# Sheet5.net
KiCad netlist of a schematic drawn in Altium Designer
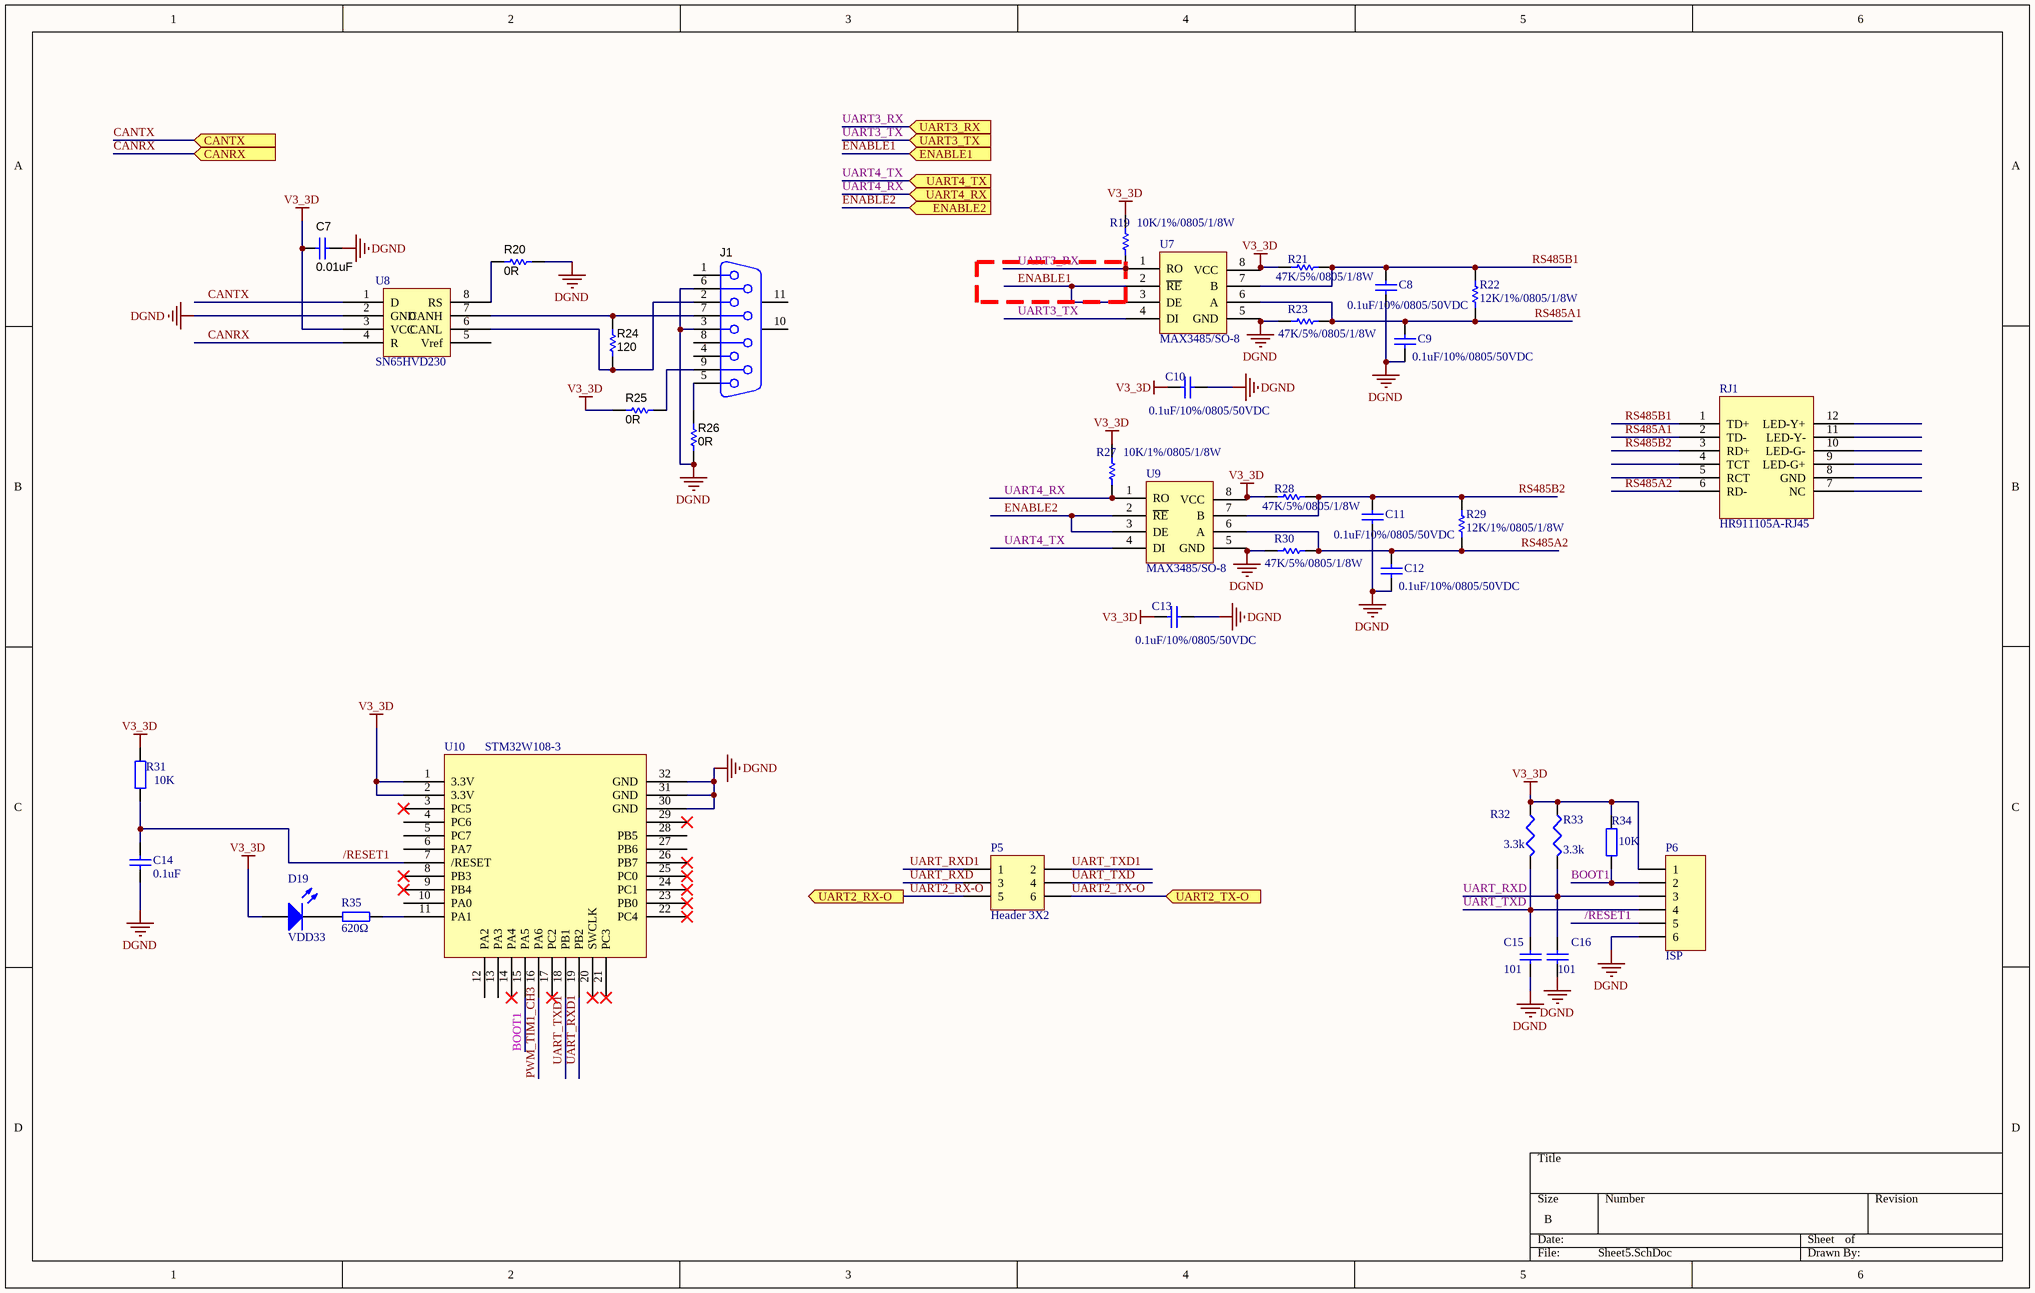
[diagram p0: Sheet5.SchDoc]

(export (version "E")
  (design (tool "Eeschema 10.0.6"))
  (components
    (comp (ref "C7")
      (value "~")
      (footprint "0805_cap")
      (description "CAP, CERM, 0.01uF, 16V, +/-10%, X7R, 0402")
      (fields
        (field (name "PARTNUMBER") "C1005X7R1C103K")
        (field (name "VALUEDISPLAYED") "0.01uF")
        (field (name "MANUFACTURER") "TDK")
        (field (name "PUBLISHER") "Texas Instruments")
      )
      (libsource (lib "Capacitor_Ceramic") (part "C1005X7R1C103K"))
    )
    (comp (ref "C8")
      (value "0.1uF/10%/0805/50VDC")
      (footprint "C-0805")
      (libsource (lib "浙江关西电机数据库") (part "CAP_Non-polarity"))
    )
    (comp (ref "C9")
      (value "0.1uF/10%/0805/50VDC")
      (footprint "C-0805")
      (libsource (lib "浙江关西电机数据库") (part "CAP_Non-polarity"))
    )
    (comp (ref "C10")
      (value "0.1uF/10%/0805/50VDC")
      (footprint "C-0805")
      (libsource (lib "浙江关西电机数据库") (part "CAP_Non-polarity"))
    )
    (comp (ref "C11")
      (value "0.1uF/10%/0805/50VDC")
      (footprint "C-0805")
      (libsource (lib "浙江关西电机数据库") (part "CAP_Non-polarity"))
    )
    (comp (ref "C12")
      (value "0.1uF/10%/0805/50VDC")
      (footprint "C-0805")
      (libsource (lib "浙江关西电机数据库") (part "CAP_Non-polarity"))
    )
    (comp (ref "C13")
      (value "0.1uF/10%/0805/50VDC")
      (footprint "C-0805")
      (libsource (lib "浙江关西电机数据库") (part "CAP_Non-polarity"))
    )
    (comp (ref "C14")
      (value "0.1uF")
      (footprint "C0805")
      (description "Capacitor")
      (fields (field (name "PUBLISHER") "Altium Limited"))
      (libsource (lib "Miscellaneous Devices") (part "Cap"))
    )
    (comp (ref "C15")
      (value "101")
      (footprint "C0805")
      (description "Capacitor")
      (fields (field (name "PUBLISHER") "Altium Limited"))
      (libsource (lib "Miscellaneous Devices") (part "Cap"))
    )
    (comp (ref "C16")
      (value "101")
      (footprint "C0805")
      (description "Capacitor")
      (fields (field (name "PUBLISHER") "Altium Limited"))
      (libsource (lib "Miscellaneous Devices") (part "Cap"))
    )
    (comp (ref "D19")
      (value "VDD33")
      (footprint "0805LED")
      (description "Typical BLUE SiC LED")
      (fields (field (name "PUBLISHER") "Altium Limited"))
      (libsource (lib "Miscellaneous Devices") (part "LED3"))
    )
    (comp (ref "J1")
      (value "~")
      (footprint "CONN_1734348-1")
      (description "Conn D-SUB RCPT R/A 9POS GOLD/FL, TH")
      (fields
        (field (name "PARTNUMBER") "1734348-1")
        (field (name "MANUFACTURER") "TE Connectivity")
        (field (name "SYMBOLCREATOR") "a0412235")
        (field (name "PUBLISHER") "Texas Instruments")
      )
      (libsource (lib "Connectors") (part "1734348-1"))
    )
    (comp (ref "P5")
      (value "Header 3X2")
      (footprint "HDR2X3")
      (description "Header, 3-Pin, Dual row")
      (fields (field (name "PUBLISHER") "Altium Limited"))
      (libsource (lib "Miscellaneous Connectors") (part "Header 3X2"))
    )
    (comp (ref "P6")
      (value "ISP")
      (footprint "SIP-6B")
      (description "Header, 6-Pin")
      (fields (field (name "PUBLISHER") "Altium Limited"))
      (libsource (lib "Miscellaneous Connectors") (part "Header 6"))
    )
    (comp (ref "R19")
      (value "10K/1%/0805/1/8W")
      (footprint "R-0805")
      (fields (field (name "PART NUMBER") "ASR-0028BA"))
      (libsource (lib "浙江关西电机数据库") (part "RES_1"))
    )
    (comp (ref "R20")
      (value "0R")
      (footprint "0805_HV")
      (description "RES, 60.4 ohm, 1%, 0.125W, 0805")
      (fields
        (field (name "PARTNUMBER") "CRCW080560R4FKEA")
        (field (name "MANUFACTURER") "Vishay-Dale")
        (field (name "PUBLISHER") "Texas Instruments")
      )
      (libsource (lib "Resistor_0805") (part "CRCW080560R4FKEA"))
    )
    (comp (ref "R21")
      (value "47K/5%/0805/1/8W")
      (footprint "R-0805")
      (fields (field (name "PART NUMBER") "ASR-0134BA"))
      (libsource (lib "浙江关西电机数据库") (part "RES_1"))
    )
    (comp (ref "R22")
      (value "12K/1%/0805/1/8W")
      (footprint "R-0805")
      (libsource (lib "浙江关西电机数据库") (part "RES_1"))
    )
    (comp (ref "R23")
      (value "47K/5%/0805/1/8W")
      (footprint "R-0805")
      (fields (field (name "PART NUMBER") "ASR-0134BA"))
      (libsource (lib "浙江关西电机数据库") (part "RES_1"))
    )
    (comp (ref "R24")
      (value "120")
      (footprint "0805_HV")
      (description "RES, 60.4 ohm, 1%, 0.125W, 0805")
      (fields
        (field (name "PARTNUMBER") "CRCW080560R4FKEA")
        (field (name "MANUFACTURER") "Vishay-Dale")
        (field (name "PUBLISHER") "Texas Instruments")
      )
      (libsource (lib "Resistor_0805") (part "CRCW080560R4FKEA"))
    )
    (comp (ref "R25")
      (value "0R")
      (footprint "0805_HV")
      (description "RES, 60.4 ohm, 1%, 0.125W, 0805")
      (fields
        (field (name "PARTNUMBER") "CRCW080560R4FKEA")
        (field (name "MANUFACTURER") "Vishay-Dale")
        (field (name "PUBLISHER") "Texas Instruments")
      )
      (libsource (lib "Resistor_0805") (part "CRCW080560R4FKEA"))
    )
    (comp (ref "R26")
      (value "0R")
      (footprint "0805_HV")
      (description "RES, 60.4 ohm, 1%, 0.125W, 0805")
      (fields
        (field (name "PARTNUMBER") "CRCW080560R4FKEA")
        (field (name "MANUFACTURER") "Vishay-Dale")
        (field (name "PUBLISHER") "Texas Instruments")
      )
      (libsource (lib "Resistor_0805") (part "CRCW080560R4FKEA"))
    )
    (comp (ref "R27")
      (value "10K/1%/0805/1/8W")
      (footprint "R-0805")
      (fields (field (name "PART NUMBER") "ASR-0028BA"))
      (libsource (lib "浙江关西电机数据库") (part "RES_1"))
    )
    (comp (ref "R28")
      (value "47K/5%/0805/1/8W")
      (footprint "R-0805")
      (fields (field (name "PART NUMBER") "ASR-0134BA"))
      (libsource (lib "浙江关西电机数据库") (part "RES_1"))
    )
    (comp (ref "R29")
      (value "12K/1%/0805/1/8W")
      (footprint "R-0805")
      (libsource (lib "浙江关西电机数据库") (part "RES_1"))
    )
    (comp (ref "R30")
      (value "47K/5%/0805/1/8W")
      (footprint "R-0805")
      (fields (field (name "PART NUMBER") "ASR-0134BA"))
      (libsource (lib "浙江关西电机数据库") (part "RES_1"))
    )
    (comp (ref "R31")
      (value "10K")
      (footprint "0805")
      (description "Resistor")
      (fields (field (name "Comment") "Res2") (field (name "PUBLISHER") "Altium Limited"))
      (libsource (lib "Miscellaneous Devices") (part "Res2"))
    )
    (comp (ref "R32")
      (value "3.3k")
      (footprint "R0805")
      (description "Resistor")
      (fields (field (name "PUBLISHER") "Altium Limited"))
      (libsource (lib "Miscellaneous Devices") (part "Res3"))
    )
    (comp (ref "R33")
      (value "3.3k")
      (footprint "R0805")
      (description "Resistor")
      (fields (field (name "PUBLISHER") "Altium Limited"))
      (libsource (lib "Miscellaneous Devices") (part "Res3"))
    )
    (comp (ref "R34")
      (value "10K")
      (footprint "R0805")
      (description "Resistor")
      (fields (field (name "Comment") "Res2") (field (name "PUBLISHER") "Altium Limited"))
      (libsource (lib "Miscellaneous Devices") (part "Res2"))
    )
    (comp (ref "R35")
      (value "620Ω")
      (footprint "R0805")
      (description "R")
      (libsource (lib "Haze") (part "RES"))
    )
    (comp (ref "RJ1")
      (value "HR911105A-RJ45")
      (footprint "HR911105A")
      (libsource (lib "moonlight") (part "HR911105A-RJ45"))
    )
    (comp (ref "U7")
      (value "MAX3485/SO-8")
      (footprint "SO-G8")
      (libsource (lib "SCHLIBRARIES") (part "MAX485"))
    )
    (comp (ref "U8")
      (value "SN65HVD230")
      (footprint "SO-G8")
      (libsource (lib "SCHLIBRARIES") (part "SN65HVD230"))
    )
    (comp (ref "U9")
      (value "MAX3485/SO-8")
      (footprint "SO-G8")
      (libsource (lib "SCHLIBRARIES") (part "MAX485"))
    )
    (comp (ref "U10")
      (value "STM32W108-3")
      (footprint "STM32W108-3")
      (libsource (lib "STM32W108-3") (part "STM32W108-3"))
    )
  )
  (nets
    (net (code "1") (name "/BOOT1") (class "Default")
      (node (ref "P6") (pin "2") (pinfunction "2_2") (pintype "passive"))
      (node (ref "R34") (pin "1") (pinfunction "1_1") (pintype "passive"))
      (node (ref "U10") (pin "15") (pinfunction "PA5_15") (pintype "passive"))
    )
    (net (code "2") (name "/CANRX") (class "Default")
      (node (ref "U8") (pin "4") (pinfunction "R_4") (pintype "passive"))
    )
    (net (code "3") (name "/CANTX") (class "Default")
      (node (ref "U8") (pin "1") (pinfunction "D_1") (pintype "passive"))
    )
    (net (code "4") (name "/ENABLE1") (class "Default")
      (node (ref "U7") (pin "2") (pinfunction "~{RE}_2") (pintype "passive"))
      (node (ref "U7") (pin "3") (pinfunction "DE_3") (pintype "passive"))
    )
    (net (code "5") (name "/ENABLE2") (class "Default")
      (node (ref "U9") (pin "2") (pinfunction "~{RE}_2") (pintype "passive"))
      (node (ref "U9") (pin "3") (pinfunction "DE_3") (pintype "passive"))
    )
    (net (code "6") (name "/PWM_TIM1_CH3") (class "Default")
      (node (ref "U10") (pin "16") (pinfunction "PA6_16") (pintype "passive"))
    )
    (net (code "7") (name "/RS485A1") (class "Default")
      (node (ref "C9") (pin "2") (pinfunction "2_2") (pintype "passive"))
      (node (ref "R22") (pin "1") (pinfunction "1_1") (pintype "passive"))
      (node (ref "R23") (pin "1") (pinfunction "1_1") (pintype "passive"))
      (node (ref "RJ1") (pin "2") (pinfunction "TD-_2") (pintype "passive"))
      (node (ref "U7") (pin "6") (pinfunction "A_6") (pintype "passive"))
    )
    (net (code "8") (name "/RS485A2") (class "Default")
      (node (ref "C12") (pin "2") (pinfunction "2_2") (pintype "passive"))
      (node (ref "R29") (pin "1") (pinfunction "1_1") (pintype "passive"))
      (node (ref "R30") (pin "1") (pinfunction "1_1") (pintype "passive"))
      (node (ref "RJ1") (pin "6") (pinfunction "RD-_6") (pintype "passive"))
      (node (ref "U9") (pin "6") (pinfunction "A_6") (pintype "passive"))
    )
    (net (code "9") (name "/RS485B1") (class "Default")
      (node (ref "C8") (pin "2") (pinfunction "2_2") (pintype "passive"))
      (node (ref "R21") (pin "1") (pinfunction "1_1") (pintype "passive"))
      (node (ref "R22") (pin "2") (pinfunction "2_2") (pintype "passive"))
      (node (ref "RJ1") (pin "1") (pinfunction "TD+_1") (pintype "passive"))
      (node (ref "U7") (pin "7") (pinfunction "B_7") (pintype "passive"))
    )
    (net (code "10") (name "/RS485B2") (class "Default")
      (node (ref "C11") (pin "2") (pinfunction "2_2") (pintype "passive"))
      (node (ref "R28") (pin "1") (pinfunction "1_1") (pintype "passive"))
      (node (ref "R29") (pin "2") (pinfunction "2_2") (pintype "passive"))
      (node (ref "RJ1") (pin "3") (pinfunction "RD+_3") (pintype "passive"))
      (node (ref "U9") (pin "7") (pinfunction "B_7") (pintype "passive"))
    )
    (net (code "11") (name "/UART2_RX-O") (class "Default")
      (node (ref "P5") (pin "5") (pinfunction "5_5") (pintype "passive"))
    )
    (net (code "12") (name "/UART2_TX-O") (class "Default")
      (node (ref "P5") (pin "6") (pinfunction "6_6") (pintype "passive"))
    )
    (net (code "13") (name "/UART3_RX") (class "Default")
      (node (ref "R19") (pin "1") (pinfunction "1_1") (pintype "passive"))
      (node (ref "U7") (pin "1") (pinfunction "RO_1") (pintype "passive"))
    )
    (net (code "14") (name "/UART3_TX") (class "Default")
      (node (ref "U7") (pin "4") (pinfunction "DI_4") (pintype "passive"))
    )
    (net (code "15") (name "/UART4_RX") (class "Default")
      (node (ref "R27") (pin "1") (pinfunction "1_1") (pintype "passive"))
      (node (ref "U9") (pin "1") (pinfunction "RO_1") (pintype "passive"))
    )
    (net (code "16") (name "/UART4_TX") (class "Default")
      (node (ref "U9") (pin "4") (pinfunction "DI_4") (pintype "passive"))
    )
    (net (code "17") (name "/UART_RXD") (class "Default")
      (node (ref "C16") (pin "2") (pinfunction "2_2") (pintype "passive"))
      (node (ref "P5") (pin "3") (pinfunction "3_3") (pintype "passive"))
      (node (ref "P6") (pin "3") (pinfunction "3_3") (pintype "passive"))
      (node (ref "R33") (pin "2") (pinfunction "2_2") (pintype "passive"))
    )
    (net (code "18") (name "/UART_RXD1") (class "Default")
      (node (ref "P5") (pin "1") (pinfunction "1_1") (pintype "passive"))
      (node (ref "U10") (pin "19") (pinfunction "PB2_19") (pintype "passive"))
    )
    (net (code "19") (name "/UART_TXD") (class "Default")
      (node (ref "C15") (pin "2") (pinfunction "2_2") (pintype "passive"))
      (node (ref "P5") (pin "4") (pinfunction "4_4") (pintype "passive"))
      (node (ref "P6") (pin "4") (pinfunction "4_4") (pintype "passive"))
      (node (ref "R32") (pin "2") (pinfunction "2_2") (pintype "passive"))
    )
    (net (code "20") (name "/UART_TXD1") (class "Default")
      (node (ref "P5") (pin "2") (pinfunction "2_2") (pintype "passive"))
      (node (ref "U10") (pin "18") (pinfunction "PB1_18") (pintype "passive"))
    )
    (net (code "21") (name "/{slash}RESET1") (class "Default")
      (node (ref "C14") (pin "2") (pinfunction "2_2") (pintype "passive"))
      (node (ref "P6") (pin "5") (pinfunction "5_5") (pintype "passive"))
      (node (ref "R31") (pin "1") (pinfunction "1_1") (pintype "passive"))
      (node (ref "U10") (pin "7") (pinfunction "/RESET_7") (pintype "passive"))
    )
    (net (code "22") (name "DGND") (class "Default")
      (node (ref "C10") (pin "2") (pinfunction "2_2") (pintype "passive"))
      (node (ref "C11") (pin "1") (pinfunction "1_1") (pintype "passive"))
      (node (ref "C12") (pin "1") (pinfunction "1_1") (pintype "passive"))
      (node (ref "C13") (pin "2") (pinfunction "2_2") (pintype "passive"))
      (node (ref "C14") (pin "1") (pinfunction "1_1") (pintype "passive"))
      (node (ref "C15") (pin "1") (pinfunction "1_1") (pintype "passive"))
      (node (ref "C16") (pin "1") (pinfunction "1_1") (pintype "passive"))
      (node (ref "C7") (pin "2") (pinfunction "2_2") (pintype "passive"))
      (node (ref "C8") (pin "1") (pinfunction "1_1") (pintype "passive"))
      (node (ref "C9") (pin "1") (pinfunction "1_1") (pintype "passive"))
      (node (ref "J1") (pin "3") (pinfunction "3_3") (pintype "passive"))
      (node (ref "J1") (pin "6") (pinfunction "6_6") (pintype "passive"))
      (node (ref "P6") (pin "6") (pinfunction "6_6") (pintype "passive"))
      (node (ref "R20") (pin "2") (pinfunction "2_2") (pintype "passive"))
      (node (ref "R23") (pin "2") (pinfunction "2_2") (pintype "passive"))
      (node (ref "R26") (pin "1") (pinfunction "1_1") (pintype "passive"))
      (node (ref "R30") (pin "2") (pinfunction "2_2") (pintype "passive"))
      (node (ref "U10") (pin "30") (pinfunction "GND_30") (pintype "passive"))
      (node (ref "U10") (pin "31") (pinfunction "GND_31") (pintype "passive"))
      (node (ref "U10") (pin "32") (pinfunction "GND_32") (pintype "passive"))
      (node (ref "U7") (pin "5") (pinfunction "GND_5") (pintype "passive"))
      (node (ref "U8") (pin "2") (pinfunction "GND_2") (pintype "passive"))
      (node (ref "U9") (pin "5") (pinfunction "GND_5") (pintype "passive"))
    )
    (net (code "23") (name "Net-(D19-K)") (class "Default")
      (node (ref "D19") (pin "2") (pinfunction "K_2") (pintype "passive"))
      (node (ref "R35") (pin "2") (pinfunction "2_2") (pintype "passive"))
    )
    (net (code "24") (name "Net-(J1-Pad5)") (class "Default")
      (node (ref "J1") (pin "5") (pinfunction "5_5") (pintype "passive"))
      (node (ref "R26") (pin "2") (pinfunction "2_2") (pintype "passive"))
    )
    (net (code "25") (name "Net-(J1-Pad9)") (class "Default")
      (node (ref "J1") (pin "9") (pinfunction "9_9") (pintype "passive"))
      (node (ref "R25") (pin "1") (pinfunction "1_1") (pintype "passive"))
    )
    (net (code "26") (name "Net-(U8-CANH)") (class "Default")
      (node (ref "J1") (pin "7") (pinfunction "7_7") (pintype "passive"))
      (node (ref "R24") (pin "1") (pinfunction "1_1") (pintype "passive"))
      (node (ref "U8") (pin "7") (pinfunction "CANH_7") (pintype "passive"))
    )
    (net (code "27") (name "Net-(U8-CANL)") (class "Default")
      (node (ref "J1") (pin "2") (pinfunction "2_2") (pintype "passive"))
      (node (ref "R24") (pin "2") (pinfunction "2_2") (pintype "passive"))
      (node (ref "U8") (pin "6") (pinfunction "CANL_6") (pintype "passive"))
    )
    (net (code "28") (name "Net-(U8-RS)") (class "Default")
      (node (ref "R20") (pin "1") (pinfunction "1_1") (pintype "passive"))
      (node (ref "U8") (pin "8") (pinfunction "RS_8") (pintype "passive"))
    )
    (net (code "29") (name "Net-(U10-PA1)") (class "Default")
      (node (ref "R35") (pin "1") (pinfunction "1_1") (pintype "passive"))
      (node (ref "U10") (pin "11") (pinfunction "PA1_11") (pintype "passive"))
    )
    (net (code "30") (name "V3_3D") (class "Default")
      (node (ref "C10") (pin "1") (pinfunction "1_1") (pintype "passive"))
      (node (ref "C13") (pin "1") (pinfunction "1_1") (pintype "passive"))
      (node (ref "C7") (pin "1") (pinfunction "1_1") (pintype "passive"))
      (node (ref "D19") (pin "1") (pinfunction "A_1") (pintype "passive"))
      (node (ref "P6") (pin "1") (pinfunction "1_1") (pintype "passive"))
      (node (ref "R19") (pin "2") (pinfunction "2_2") (pintype "passive"))
      (node (ref "R21") (pin "2") (pinfunction "2_2") (pintype "passive"))
      (node (ref "R25") (pin "2") (pinfunction "2_2") (pintype "passive"))
      (node (ref "R27") (pin "2") (pinfunction "2_2") (pintype "passive"))
      (node (ref "R28") (pin "2") (pinfunction "2_2") (pintype "passive"))
      (node (ref "R31") (pin "2") (pinfunction "2_2") (pintype "passive"))
      (node (ref "R32") (pin "1") (pinfunction "1_1") (pintype "passive"))
      (node (ref "R33") (pin "1") (pinfunction "1_1") (pintype "passive"))
      (node (ref "R34") (pin "2") (pinfunction "2_2") (pintype "passive"))
      (node (ref "U10") (pin "1") (pinfunction "3.3V_1") (pintype "passive"))
      (node (ref "U10") (pin "2") (pinfunction "3.3V_2") (pintype "passive"))
      (node (ref "U7") (pin "8") (pinfunction "VCC_8") (pintype "passive"))
      (node (ref "U8") (pin "3") (pinfunction "VCC_3") (pintype "passive"))
      (node (ref "U9") (pin "8") (pinfunction "VCC_8") (pintype "passive"))
    )
    (net (code "31") (name "unconnected-(J1-MH1-Pad10)") (class "Default")
      (node (ref "J1") (pin "10") (pinfunction "MH1_10") (pintype "passive"))
    )
    (net (code "32") (name "unconnected-(J1-MH2-Pad11)") (class "Default")
      (node (ref "J1") (pin "11") (pinfunction "MH2_11") (pintype "passive"))
    )
    (net (code "33") (name "unconnected-(J1-Pad1)") (class "Default")
      (node (ref "J1") (pin "1") (pinfunction "1_1") (pintype "passive"))
    )
    (net (code "34") (name "unconnected-(J1-Pad4)") (class "Default")
      (node (ref "J1") (pin "4") (pinfunction "4_4") (pintype "passive"))
    )
    (net (code "35") (name "unconnected-(J1-Pad8)") (class "Default")
      (node (ref "J1") (pin "8") (pinfunction "8_8") (pintype "passive"))
    )
    (net (code "36") (name "unconnected-(RJ1-GND-Pad8)") (class "Default")
      (node (ref "RJ1") (pin "8") (pinfunction "GND_8") (pintype "passive"))
    )
    (net (code "37") (name "unconnected-(RJ1-LED-G+-Pad9)") (class "Default")
      (node (ref "RJ1") (pin "9") (pinfunction "LED-G+_9") (pintype "passive"))
    )
    (net (code "38") (name "unconnected-(RJ1-LED-G--Pad10)") (class "Default")
      (node (ref "RJ1") (pin "10") (pinfunction "LED-G-_10") (pintype "passive"))
    )
    (net (code "39") (name "unconnected-(RJ1-LED-Y+-Pad12)") (class "Default")
      (node (ref "RJ1") (pin "12") (pinfunction "LED-Y+_12") (pintype "passive"))
    )
    (net (code "40") (name "unconnected-(RJ1-LED-Y--Pad11)") (class "Default")
      (node (ref "RJ1") (pin "11") (pinfunction "LED-Y-_11") (pintype "passive"))
    )
    (net (code "41") (name "unconnected-(RJ1-NC-Pad7)") (class "Default")
      (node (ref "RJ1") (pin "7") (pinfunction "NC_7") (pintype "passive"))
    )
    (net (code "42") (name "unconnected-(RJ1-RCT-Pad5)") (class "Default")
      (node (ref "RJ1") (pin "5") (pinfunction "RCT_5") (pintype "passive"))
    )
    (net (code "43") (name "unconnected-(RJ1-TCT-Pad4)") (class "Default")
      (node (ref "RJ1") (pin "4") (pinfunction "TCT_4") (pintype "passive"))
    )
    (net (code "44") (name "unconnected-(U8-Vref-Pad5)") (class "Default")
      (node (ref "U8") (pin "5") (pinfunction "Vref_5") (pintype "passive"))
    )
    (net (code "45") (name "unconnected-(U10-PA0-Pad10)") (class "Default")
      (node (ref "U10") (pin "10") (pinfunction "PA0_10") (pintype "passive"))
    )
    (net (code "46") (name "unconnected-(U10-PA2-Pad12)") (class "Default")
      (node (ref "U10") (pin "12") (pinfunction "PA2_12") (pintype "passive"))
    )
    (net (code "47") (name "unconnected-(U10-PA3-Pad13)") (class "Default")
      (node (ref "U10") (pin "13") (pinfunction "PA3_13") (pintype "passive"))
    )
    (net (code "48") (name "unconnected-(U10-PA4-Pad14)") (class "Default")
      (node (ref "U10") (pin "14") (pinfunction "PA4_14") (pintype "passive+no_connect"))
    )
    (net (code "49") (name "unconnected-(U10-PA7-Pad6)") (class "Default")
      (node (ref "U10") (pin "6") (pinfunction "PA7_6") (pintype "passive"))
    )
    (net (code "50") (name "unconnected-(U10-PB0-Pad23)") (class "Default")
      (node (ref "U10") (pin "23") (pinfunction "PB0_23") (pintype "passive+no_connect"))
    )
    (net (code "51") (name "unconnected-(U10-PB3-Pad8)") (class "Default")
      (node (ref "U10") (pin "8") (pinfunction "PB3_8") (pintype "passive+no_connect"))
    )
    (net (code "52") (name "unconnected-(U10-PB4-Pad9)") (class "Default")
      (node (ref "U10") (pin "9") (pinfunction "PB4_9") (pintype "passive+no_connect"))
    )
    (net (code "53") (name "unconnected-(U10-PB5-Pad28)") (class "Default")
      (node (ref "U10") (pin "28") (pinfunction "PB5_28") (pintype "passive"))
    )
    (net (code "54") (name "unconnected-(U10-PB6-Pad27)") (class "Default")
      (node (ref "U10") (pin "27") (pinfunction "PB6_27") (pintype "passive"))
    )
    (net (code "55") (name "unconnected-(U10-PB7-Pad26)") (class "Default")
      (node (ref "U10") (pin "26") (pinfunction "PB7_26") (pintype "passive+no_connect"))
    )
    (net (code "56") (name "unconnected-(U10-PC0-Pad25)") (class "Default")
      (node (ref "U10") (pin "25") (pinfunction "PC0_25") (pintype "passive+no_connect"))
    )
    (net (code "57") (name "unconnected-(U10-PC1-Pad24)") (class "Default")
      (node (ref "U10") (pin "24") (pinfunction "PC1_24") (pintype "passive+no_connect"))
    )
    (net (code "58") (name "unconnected-(U10-PC2-Pad17)") (class "Default")
      (node (ref "U10") (pin "17") (pinfunction "PC2_17") (pintype "passive+no_connect"))
    )
    (net (code "59") (name "unconnected-(U10-PC3-Pad21)") (class "Default")
      (node (ref "U10") (pin "21") (pinfunction "PC3_21") (pintype "passive+no_connect"))
    )
    (net (code "60") (name "unconnected-(U10-PC4-Pad22)") (class "Default")
      (node (ref "U10") (pin "22") (pinfunction "PC4_22") (pintype "passive+no_connect"))
    )
    (net (code "61") (name "unconnected-(U10-PC5-Pad3)") (class "Default")
      (node (ref "U10") (pin "3") (pinfunction "PC5_3") (pintype "passive+no_connect"))
    )
    (net (code "62") (name "unconnected-(U10-PC6-Pad4)") (class "Default")
      (node (ref "U10") (pin "4") (pinfunction "PC6_4") (pintype "passive"))
    )
    (net (code "63") (name "unconnected-(U10-PC7-Pad5)") (class "Default")
      (node (ref "U10") (pin "5") (pinfunction "PC7_5") (pintype "passive"))
    )
    (net (code "64") (name "unconnected-(U10-Pad29)") (class "Default")
      (node (ref "U10") (pin "29") (pintype "passive+no_connect"))
    )
    (net (code "65") (name "unconnected-(U10-SWCLK-Pad20)") (class "Default")
      (node (ref "U10") (pin "20") (pinfunction "SWCLK_20") (pintype "passive+no_connect"))
    )
  )
)
